# Power_Distribution_-_ADC.net
KiCad netlist of a schematic drawn in Altium Designer
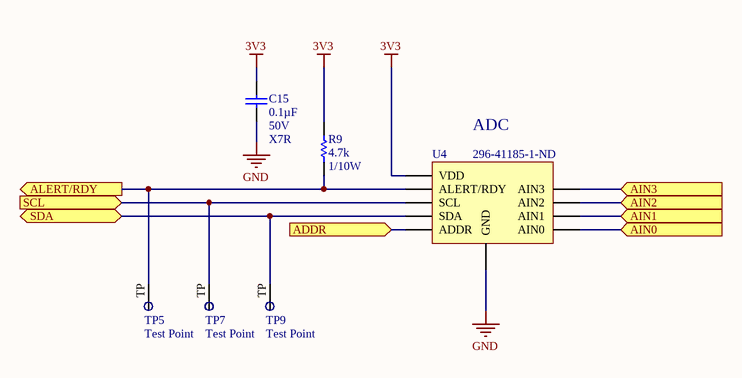
[diagram p0: Power Distribution - ADC.SchDoc]

(export (version "E")
  (design (tool "Eeschema 10.0.6"))
  (components
    (comp (ref "C15")
      (value "CAP CER 0.1UF 50V 10% X7R 0603")
      (footprint "CAP, 0603")
      (description "0.10µF ±10% 50V Ceramic Capacitor X7R 0603 (1608 Metric)")
      (fields
        (field (name "TOLERANCE") "±10%")
        (field (name "CAPACITANCE") "0.1µF")
        (field (name "VOLTAGE") "50V")
        (field (name "TEMPERATURE COEFFICIENT") "X7R")
      )
      (libsource (lib "Schematic Diagrams") (part "CAP CER 0.1UF 50V 10% X7R 0603"))
    )
    (comp (ref "R9")
      (value "RES 4.7K OHM 1% 1/10W 0603")
      (footprint "RES, 0603")
      (description "4.7k Ohm ±1% 0.1W, 1/10W Chip Resistor 0603 (1608 Metric) Moisture Resistant Thick Film")
      (fields
        (field (name "TOLERANCE") "±1%")
        (field (name "RESISTANCE (OHMS)") "4.7k")
        (field (name "POWER (WATTS)") "1/10W")
      )
      (libsource (lib "Schematic Diagrams") (part "RES 4.7K OHM 1% 1/10W 0603"))
    )
    (comp (ref "TP5")
      (value "Test Point")
      (footprint "Test Point")
      (libsource (lib "Schematic Diagrams") (part "Test Point"))
    )
    (comp (ref "TP7")
      (value "Test Point")
      (footprint "Test Point")
      (libsource (lib "Schematic Diagrams") (part "Test Point"))
    )
    (comp (ref "TP9")
      (value "Test Point")
      (footprint "Test Point")
      (libsource (lib "Schematic Diagrams") (part "Test Point"))
    )
    (comp (ref "U4")
      (value "Quad ADC")
      (footprint "IC ADC VSSOP10")
      (description "12 Bit Analog to Digital Converter 4 Input 1 Sigma-Delta 10-VSSOP")
      (fields
        (field (name "MANUFACTURER") "Texas Instruments")
        (field (name "MANUFACTURER PART NUMBER") "ADS1015IDGSR")
        (field (name "SUPPLIER PART NUMBER 1") "296-41185-1-ND")
      )
      (libsource (lib "Schematic Diagrams") (part "IC ADC 12-BIT VSSOP-10"))
    )
  )
  (nets
    (net (code "1") (name "/ADDR") (class "Default")
      (node (ref "U4") (pin "1") (pinfunction "ADDR_1") (pintype "passive"))
    )
    (net (code "2") (name "/AIN0") (class "Default")
      (node (ref "U4") (pin "4") (pinfunction "AIN0_4") (pintype "passive"))
    )
    (net (code "3") (name "/AIN1") (class "Default")
      (node (ref "U4") (pin "5") (pinfunction "AIN1_5") (pintype "passive"))
    )
    (net (code "4") (name "/AIN2") (class "Default")
      (node (ref "U4") (pin "6") (pinfunction "AIN2_6") (pintype "passive"))
    )
    (net (code "5") (name "/AIN3") (class "Default")
      (node (ref "U4") (pin "7") (pinfunction "AIN3_7") (pintype "passive"))
    )
    (net (code "6") (name "/ALERT{slash}RDY") (class "Default")
      (node (ref "R9") (pin "2") (pinfunction "2_2") (pintype "passive"))
      (node (ref "TP5") (pin "TP") (pinfunction "1_TP") (pintype "passive"))
      (node (ref "U4") (pin "2") (pinfunction "ALERT/RDY_2") (pintype "passive"))
    )
    (net (code "7") (name "/SCL") (class "Default")
      (node (ref "TP7") (pin "TP") (pinfunction "1_TP") (pintype "passive"))
      (node (ref "U4") (pin "10") (pinfunction "SCL_10") (pintype "passive"))
    )
    (net (code "8") (name "/SDA") (class "Default")
      (node (ref "TP9") (pin "TP") (pinfunction "1_TP") (pintype "passive"))
      (node (ref "U4") (pin "9") (pinfunction "SDA_9") (pintype "passive"))
    )
    (net (code "9") (name "3V3") (class "Default")
      (node (ref "C15") (pin "1") (pinfunction "1_1") (pintype "passive"))
      (node (ref "R9") (pin "1") (pinfunction "1_1") (pintype "passive"))
      (node (ref "U4") (pin "8") (pinfunction "VDD_8") (pintype "passive"))
    )
    (net (code "10") (name "GND") (class "Default")
      (node (ref "C15") (pin "2") (pinfunction "2_2") (pintype "passive"))
      (node (ref "U4") (pin "3") (pinfunction "GND_3") (pintype "passive"))
    )
  )
)
